# WR_LINK.net
KiCad netlist of a schematic drawn in Altium Designer
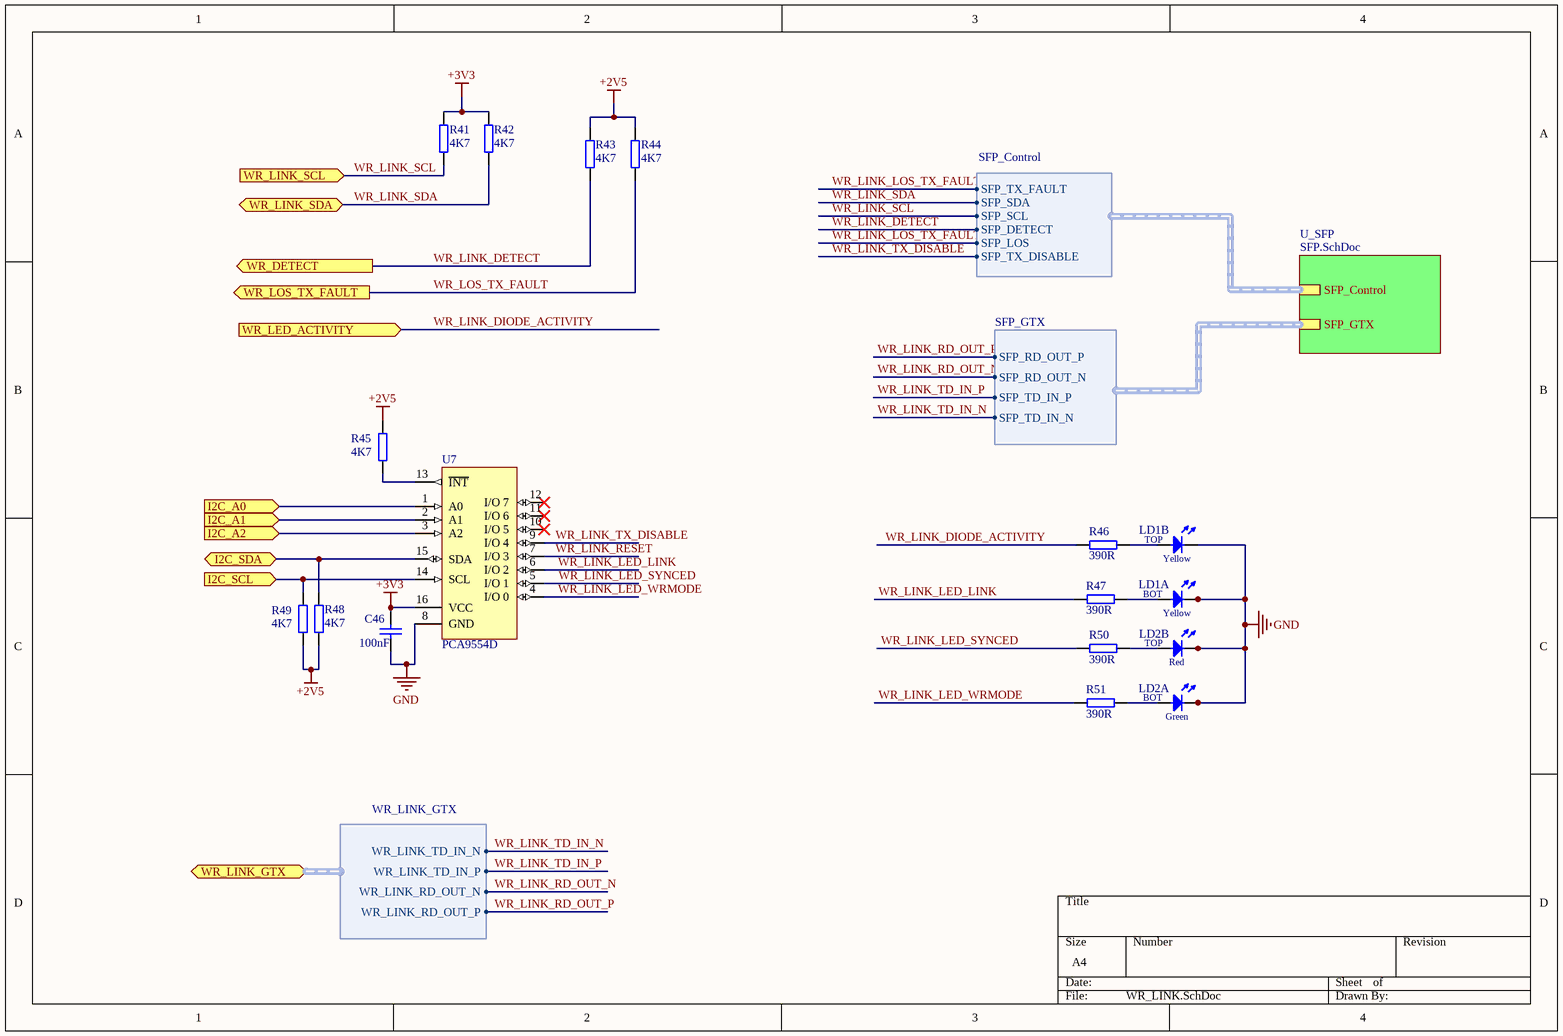
[diagram p0: WR_LINK.SchDoc]

(export (version "E")
  (design (tool "Eeschema 10.0.6"))
  (components
    (comp (ref "C46")
      (value "100nF")
      (footprint "CC1608-0603")
      (description "Capacitor")
      (fields
        (field (name "TOLERANCE") "±10%")
        (field (name "VOLTAGE") "16V")
        (field (name "PUBLISHER") "Altium Limited")
      )
      (libsource (lib "wr_switch") (part "Cap"))
    )
    (comp (ref "LD1")
      (value "Yellow/Yellow")
      (footprint "LED_DIALIGHT_571-0133-100F")
      (description "LED x2 Yellow 1C2A-BOT_3C4A-TOP")
      (fields
        (field (name "PART NUMBER") "LED_DIALIGHT_571-0133-100F")
        (field (name "MANUFACTURER") "DIALIGHT")
        (field (name "AUTHOR") "CERN DEM JLC")
      )
      (libsource (lib "ICs And Semiconductors") (part "LED x2 Yellow 1C2A-BOT_3C4A-TOP"))
    )
    (comp (ref "LD2")
      (value "Green/Yellow")
      (footprint "LED_DIALIGHT_571-0132-100F")
      (description "2x LED  Botom Green, Top Yellow")
      (fields
        (field (name "PART NUMBER") "LED_DIALIGHT_571-0132-100F")
        (field (name "MANUFACTURER") "DIALIGHT")
        (field (name "AUTHOR") "CERN DEM JLC")
      )
      (libsource (lib "ICs And Semiconductors") (part "LED x2 G-1C2A-BOT_Y-3C4A-TOP"))
    )
    (comp (ref "R41")
      (value "4K7")
      (footprint "0402")
      (description "SMD Resistor")
      (fields (field (name "TOLERANCE") "±1%"))
      (libsource (lib "wr_switch") (part "RES_SMD"))
    )
    (comp (ref "R42")
      (value "4K7")
      (footprint "0402")
      (description "SMD Resistor")
      (fields (field (name "TOLERANCE") "±1%"))
      (libsource (lib "wr_switch") (part "RES_SMD"))
    )
    (comp (ref "R43")
      (value "4K7")
      (footprint "0402")
      (description "SMD Resistor")
      (fields (field (name "TOLERANCE") "±1%"))
      (libsource (lib "wr_switch") (part "RES_SMD"))
    )
    (comp (ref "R44")
      (value "4K7")
      (footprint "0402")
      (description "SMD Resistor")
      (fields (field (name "TOLERANCE") "±1%"))
      (libsource (lib "wr_switch") (part "RES_SMD"))
    )
    (comp (ref "R45")
      (value "4K7")
      (footprint "0603")
      (description "SMD Resistor")
      (fields (field (name "TOLERANCE") "±1%"))
      (libsource (lib "wr_switch") (part "RES_SMD"))
    )
    (comp (ref "R46")
      (value "390R")
      (footprint "0603")
      (description "SMD Resistor")
      (fields (field (name "TOLERANCE") "±1%"))
      (libsource (lib "wr_switch") (part "RES_SMD"))
    )
    (comp (ref "R47")
      (value "390R")
      (footprint "0603")
      (description "SMD Resistor")
      (fields (field (name "TOLERANCE") "±1%"))
      (libsource (lib "wr_switch") (part "RES_SMD"))
    )
    (comp (ref "R48")
      (value "4K7")
      (footprint "0603")
      (description "SMD Resistor")
      (fields (field (name "TOLERANCE") "±1%"))
      (libsource (lib "wr_switch") (part "RES_SMD"))
    )
    (comp (ref "R49")
      (value "4K7")
      (footprint "0603")
      (description "SMD Resistor")
      (fields (field (name "TOLERANCE") "±1%"))
      (libsource (lib "wr_switch") (part "RES_SMD"))
    )
    (comp (ref "R50")
      (value "390R")
      (footprint "0603")
      (description "SMD Resistor")
      (fields (field (name "TOLERANCE") "±1%"))
      (libsource (lib "wr_switch") (part "RES_SMD"))
    )
    (comp (ref "R51")
      (value "390R")
      (footprint "0603")
      (description "SMD Resistor")
      (fields (field (name "TOLERANCE") "±1%"))
      (libsource (lib "wr_switch") (part "RES_SMD"))
    )
    (comp (ref "U7")
      (value "PCA9554D")
      (footprint "SOP65P640X110-20N")
      (description "8-bit I2C-bus SMBus I/O port with interrupt")
      (libsource (lib "wr_switch") (part "PCA9554D"))
    )
  )
  (nets
    (net (code "4") (name "+2V5") (class "Default")
      (node (ref "R43") (pin "2") (pinfunction "2_2") (pintype "passive"))
      (node (ref "R44") (pin "2") (pinfunction "2_2") (pintype "passive"))
      (node (ref "R45") (pin "2") (pinfunction "2_2") (pintype "passive"))
      (node (ref "R48") (pin "2") (pinfunction "2_2") (pintype "passive"))
      (node (ref "R49") (pin "1") (pinfunction "1_1") (pintype "passive"))
    )
    (net (code "5") (name "+3V3") (class "Default")
      (node (ref "C46") (pin "1") (pinfunction "1_1") (pintype "passive"))
      (node (ref "R41") (pin "2") (pinfunction "2_2") (pintype "passive"))
      (node (ref "R42") (pin "2") (pinfunction "2_2") (pintype "passive"))
      (node (ref "U7") (pin "16") (pinfunction "VCC_16") (pintype "power_in"))
    )
    (net (code "6") (name "/I2C_A0") (class "Default")
      (node (ref "U7") (pin "1") (pinfunction "A0_1") (pintype "input"))
    )
    (net (code "7") (name "/I2C_A1") (class "Default")
      (node (ref "U7") (pin "2") (pinfunction "A1_2") (pintype "input"))
    )
    (net (code "8") (name "/I2C_A2") (class "Default")
      (node (ref "U7") (pin "3") (pinfunction "A2_3") (pintype "input"))
    )
    (net (code "9") (name "/I2C_SCL") (class "Default")
      (node (ref "R49") (pin "2") (pinfunction "2_2") (pintype "passive"))
      (node (ref "U7") (pin "14") (pinfunction "SCL_14") (pintype "input"))
    )
    (net (code "10") (name "/I2C_SDA") (class "Default")
      (node (ref "R48") (pin "1") (pinfunction "1_1") (pintype "passive"))
      (node (ref "U7") (pin "15") (pinfunction "SDA_15") (pintype "bidirectional"))
    )
    (net (code "11") (name "/WR_LINK_DETECT") (class "Default")
      (node (ref "R43") (pin "1") (pinfunction "1_1") (pintype "passive"))
    )
    (net (code "12") (name "/WR_LINK_DIODE_ACTIVITY") (class "Default")
      (node (ref "R46") (pin "2") (pinfunction "2_2") (pintype "passive"))
    )
    (net (code "13") (name "/WR_LINK_LED_LINK") (class "Default")
      (node (ref "R47") (pin "2") (pinfunction "2_2") (pintype "passive"))
      (node (ref "U7") (pin "6") (pinfunction "I/O_2_6") (pintype "bidirectional"))
    )
    (net (code "14") (name "/WR_LINK_LED_SYNCED") (class "Default")
      (node (ref "R50") (pin "2") (pinfunction "2_2") (pintype "passive"))
      (node (ref "U7") (pin "5") (pinfunction "I/O_1_5") (pintype "bidirectional"))
    )
    (net (code "15") (name "/WR_LINK_LED_WRMODE") (class "Default")
      (node (ref "R51") (pin "2") (pinfunction "2_2") (pintype "passive"))
      (node (ref "U7") (pin "4") (pinfunction "I/O_0_4") (pintype "bidirectional"))
    )
    (net (code "19") (name "/WR_LINK_RESET") (class "Default")
      (node (ref "U7") (pin "7") (pinfunction "I/O_3_7") (pintype "bidirectional"))
    )
    (net (code "20") (name "/WR_LINK_SCL") (class "Default")
      (node (ref "R41") (pin "1") (pinfunction "1_1") (pintype "passive"))
    )
    (net (code "21") (name "/WR_LINK_SDA") (class "Default")
      (node (ref "R42") (pin "1") (pinfunction "1_1") (pintype "passive"))
    )
    (net (code "24") (name "/WR_LINK_TX_DISABLE") (class "Default")
      (node (ref "U7") (pin "9") (pinfunction "I/O_4_9") (pintype "bidirectional"))
    )
    (net (code "25") (name "/WR_LOS_TX_FAULT") (class "Default")
      (node (ref "R44") (pin "1") (pinfunction "1_1") (pintype "passive"))
    )
    (net (code "29") (name "GND") (class "Default")
      (node (ref "C46") (pin "2") (pinfunction "2_2") (pintype "passive"))
      (node (ref "LD1") (pin "1") (pinfunction "C_1") (pintype "passive"))
      (node (ref "LD1") (pin "3") (pinfunction "C_3") (pintype "passive"))
      (node (ref "LD2") (pin "1") (pinfunction "C_1") (pintype "passive"))
      (node (ref "LD2") (pin "3") (pinfunction "C_3") (pintype "passive"))
      (node (ref "U7") (pin "8") (pinfunction "GND_8") (pintype "power_in"))
    )
    (net (code "30") (name "Net-(LD1A-A)") (class "Default")
      (node (ref "LD1") (pin "2") (pinfunction "A_2") (pintype "passive"))
      (node (ref "R47") (pin "1") (pinfunction "1_1") (pintype "passive"))
    )
    (net (code "31") (name "Net-(LD1B-A)") (class "Default")
      (node (ref "LD1") (pin "4") (pinfunction "A_4") (pintype "passive"))
      (node (ref "R46") (pin "1") (pinfunction "1_1") (pintype "passive"))
    )
    (net (code "32") (name "Net-(LD2A-A)") (class "Default")
      (node (ref "LD2") (pin "2") (pinfunction "A_2") (pintype "passive"))
      (node (ref "R51") (pin "1") (pinfunction "1_1") (pintype "passive"))
    )
    (net (code "33") (name "Net-(LD2B-A)") (class "Default")
      (node (ref "LD2") (pin "4") (pinfunction "A_4") (pintype "passive"))
      (node (ref "R50") (pin "1") (pinfunction "1_1") (pintype "passive"))
    )
    (net (code "34") (name "Net-(U7-~{INT})") (class "Default")
      (node (ref "R45") (pin "1") (pinfunction "1_1") (pintype "passive"))
      (node (ref "U7") (pin "13") (pinfunction "~{INT}_13") (pintype "output"))
    )
    (net (code "35") (name "unconnected-(U7-I{slash}O_5-Pad10)") (class "Default")
      (node (ref "U7") (pin "10") (pinfunction "I/O_5_10") (pintype "bidirectional+no_connect"))
    )
    (net (code "36") (name "unconnected-(U7-I{slash}O_6-Pad11)") (class "Default")
      (node (ref "U7") (pin "11") (pinfunction "I/O_6_11") (pintype "bidirectional+no_connect"))
    )
    (net (code "37") (name "unconnected-(U7-I{slash}O_7-Pad12)") (class "Default")
      (node (ref "U7") (pin "12") (pinfunction "I/O_7_12") (pintype "bidirectional+no_connect"))
    )
  )
)
